# MP2456_EVM_V1.net
KiCad netlist of a schematic drawn in EAGLE
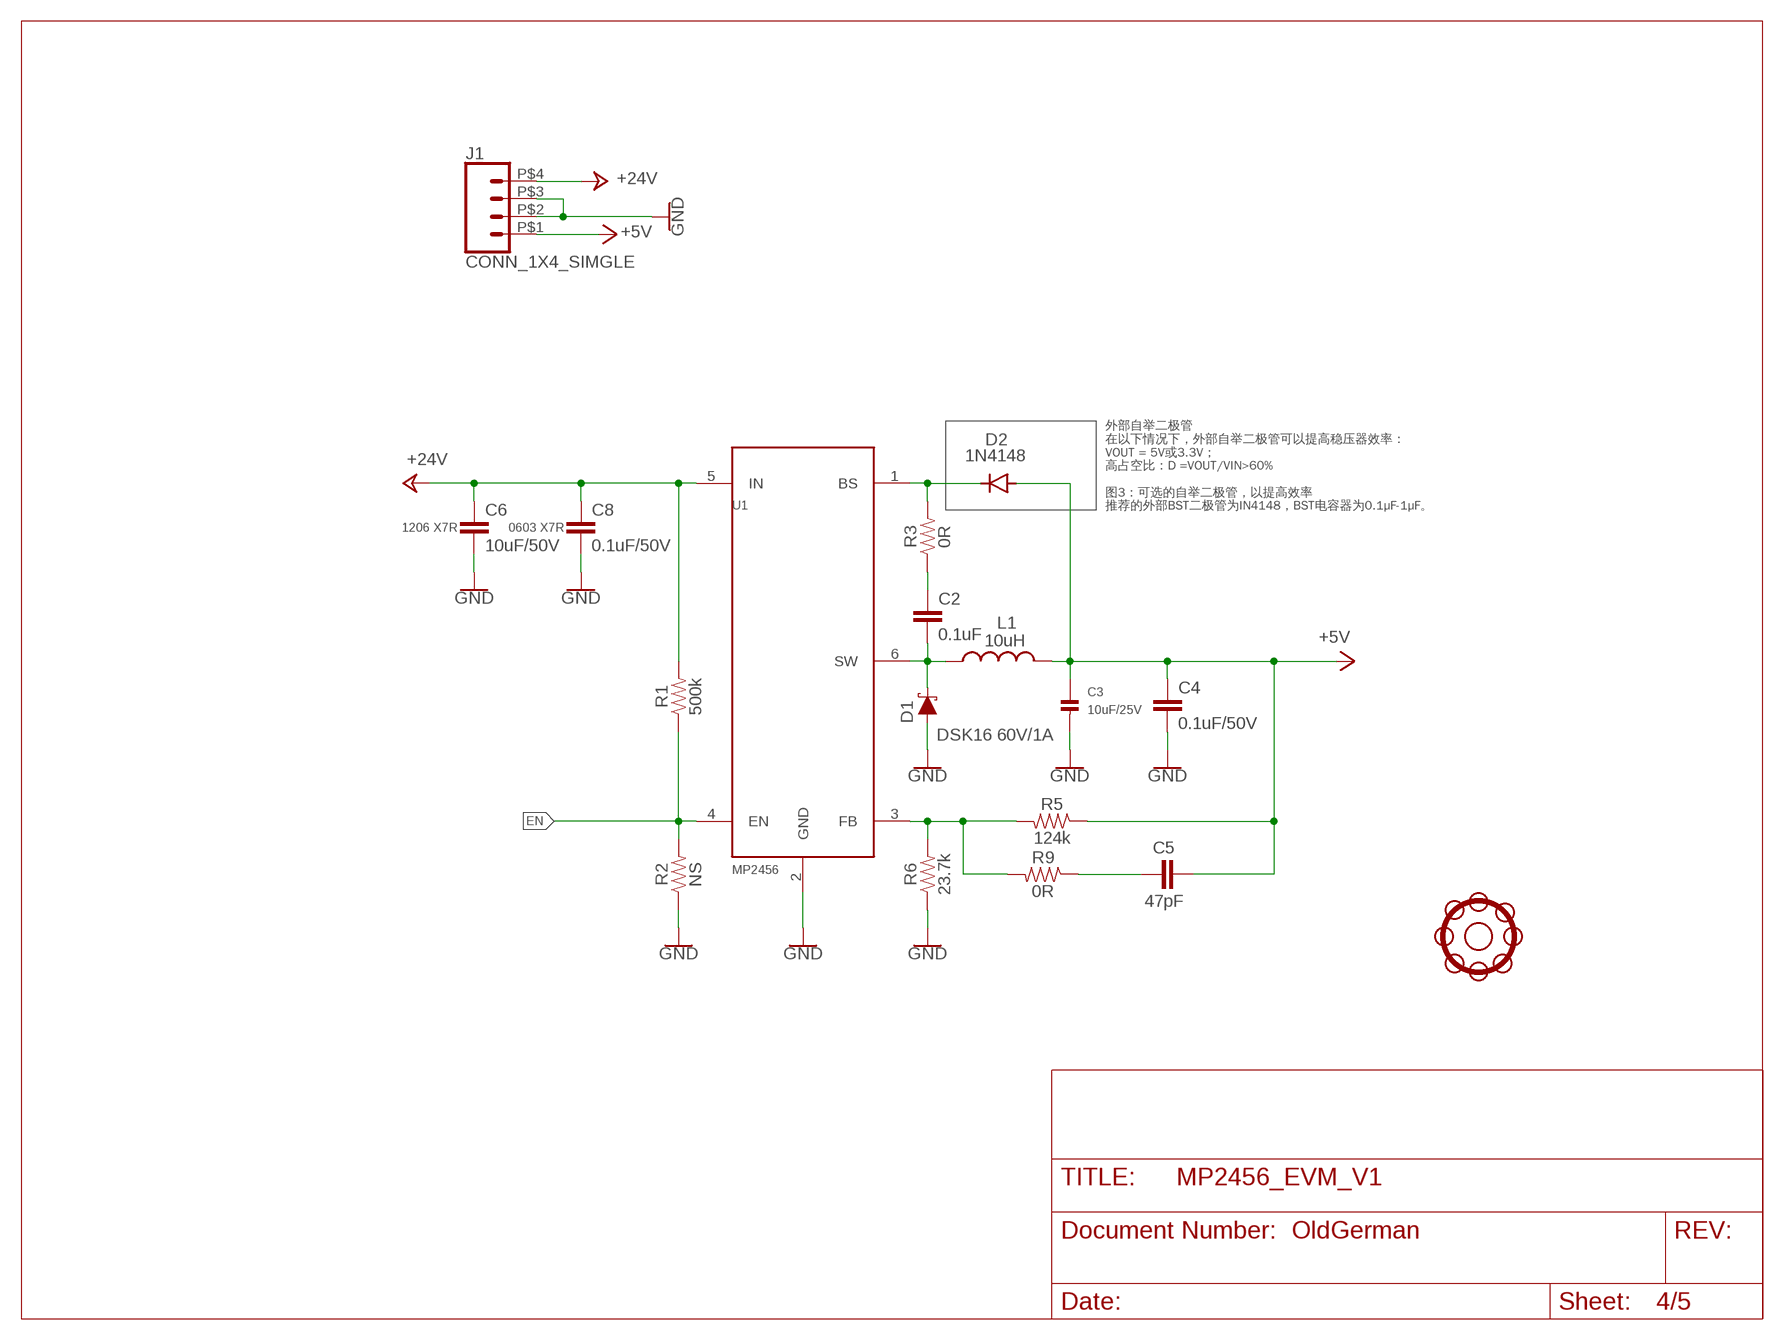
[diagram p0: schematic, sheet 4]

(export (version "E")
  (design (tool "Eeschema 10.0.6"))
  (components
    (comp (ref "C2")
      (value "0.1uF")
      (footprint "eagle-import:0603")
      (libsource (lib "eagle-import") (part "CAP-0603"))
    )
    (comp (ref "C3")
      (value "10uF/25V")
      (footprint "eagle-import:_0805MP")
      (libsource (lib "eagle-import") (part "CAP_CERAMIC_0805MP"))
    )
    (comp (ref "C4")
      (value "0.1uF/50V")
      (footprint "eagle-import:0603")
      (libsource (lib "eagle-import") (part "CAP-0603"))
    )
    (comp (ref "C5")
      (value "47pF")
      (footprint "eagle-import:0603")
      (libsource (lib "eagle-import") (part "CAP-0603"))
    )
    (comp (ref "C6")
      (value "10uF/50V")
      (footprint "eagle-import:1206")
      (libsource (lib "eagle-import") (part "CAP-1206"))
    )
    (comp (ref "C8")
      (value "0.1uF/50V")
      (footprint "eagle-import:0603")
      (libsource (lib "eagle-import") (part "CAP-0603"))
    )
    (comp (ref "D1")
      (value "DSK16 60V/1A")
      (footprint "eagle-import:SOD123")
      (libsource (lib "eagle-import") (part "B5819W-SOD123"))
    )
    (comp (ref "D2")
      (value "1N4148")
      (footprint "eagle-import:SOD123")
      (libsource (lib "eagle-import") (part "DIODE-SOD123"))
    )
    (comp (ref "J1")
      (value "CONN_1X4_SIMGLE")
      (footprint "eagle-import:CONN_1X04_SINGLE")
      (libsource (lib "eagle-import") (part "CONN_1X4_SIMGLE"))
    )
    (comp (ref "L1")
      (value "10uH")
      (footprint "eagle-import:4020TYPE")
      (libsource (lib "eagle-import") (part "INDUCTOR_4040"))
    )
    (comp (ref "R1")
      (value "500k")
      (footprint "eagle-import:0603")
      (libsource (lib "eagle-import") (part "RESISTOR0603"))
    )
    (comp (ref "R2")
      (value "NS")
      (footprint "eagle-import:0603")
      (libsource (lib "eagle-import") (part "RESISTOR0603"))
    )
    (comp (ref "R3")
      (value "0R")
      (footprint "eagle-import:0603")
      (libsource (lib "eagle-import") (part "RESISTOR0603"))
    )
    (comp (ref "R5")
      (value "124k")
      (footprint "eagle-import:0603")
      (libsource (lib "eagle-import") (part "RESISTOR0603"))
    )
    (comp (ref "R6")
      (value "23.7k")
      (footprint "eagle-import:0603")
      (libsource (lib "eagle-import") (part "RESISTOR0603"))
    )
    (comp (ref "R9")
      (value "0R")
      (footprint "eagle-import:0603")
      (libsource (lib "eagle-import") (part "RESISTOR0603"))
    )
    (comp (ref "U$1")
      (value "SUN_HOLE_M3")
      (footprint "eagle-import:SUN_HOLE_M3")
      (libsource (lib "eagle-import") (part "SUN_HOLE_M3"))
    )
    (comp (ref "U1")
      (value "MP2456")
      (footprint "eagle-import:SOT23-6")
      (libsource (lib "eagle-import") (part "MP2456"))
    )
  )
  (nets
    (net (code "1") (name "+5V") (class "Default")
      (node (ref "C3") (pin "1") (pinfunction "P$1_1") (pintype "passive"))
      (node (ref "C4") (pin "1") (pinfunction "1_1") (pintype "passive"))
      (node (ref "C5") (pin "2") (pinfunction "2_2") (pintype "passive"))
      (node (ref "D2") (pin "A") (pinfunction "A_A") (pintype "passive"))
      (node (ref "J1") (pin "P$1") (pinfunction "1_P$1") (pintype "passive"))
      (node (ref "L1") (pin "P$2") (pinfunction "2_P$2") (pintype "passive"))
      (node (ref "R5") (pin "1") (pinfunction "1_1") (pintype "passive"))
    )
    (net (code "2") (name "+24V") (class "Default")
      (node (ref "C6") (pin "1") (pinfunction "1_1") (pintype "passive"))
      (node (ref "C8") (pin "1") (pinfunction "1_1") (pintype "passive"))
      (node (ref "J1") (pin "P$4") (pinfunction "4_P$4") (pintype "passive"))
      (node (ref "R1") (pin "2") (pinfunction "2_2") (pintype "passive"))
      (node (ref "U1") (pin "5") (pinfunction "IN_5") (pintype "bidirectional"))
    )
    (net (code "3") (name "EN") (class "Default")
      (node (ref "R1") (pin "1") (pinfunction "1_1") (pintype "passive"))
      (node (ref "R2") (pin "2") (pinfunction "2_2") (pintype "passive"))
      (node (ref "U1") (pin "4") (pinfunction "EN_4") (pintype "bidirectional"))
    )
    (net (code "4") (name "GND") (class "Default")
      (node (ref "C3") (pin "2") (pinfunction "P$2_2") (pintype "passive"))
      (node (ref "C4") (pin "2") (pinfunction "2_2") (pintype "passive"))
      (node (ref "C6") (pin "2") (pinfunction "2_2") (pintype "passive"))
      (node (ref "C8") (pin "2") (pinfunction "2_2") (pintype "passive"))
      (node (ref "D1") (pin "A") (pinfunction "A_A") (pintype "passive"))
      (node (ref "J1") (pin "P$2") (pinfunction "2_P$2") (pintype "passive"))
      (node (ref "J1") (pin "P$3") (pinfunction "3_P$3") (pintype "passive"))
      (node (ref "R2") (pin "1") (pinfunction "1_1") (pintype "passive"))
      (node (ref "R6") (pin "1") (pinfunction "1_1") (pintype "passive"))
      (node (ref "U1") (pin "2") (pinfunction "GND_2") (pintype "bidirectional"))
    )
    (net (code "5") (name "Net-(C2-Pad1)") (class "Default")
      (node (ref "C2") (pin "1") (pinfunction "1_1") (pintype "passive"))
      (node (ref "R3") (pin "1") (pinfunction "1_1") (pintype "passive"))
    )
    (net (code "6") (name "Net-(C5-Pad1)") (class "Default")
      (node (ref "C5") (pin "1") (pinfunction "1_1") (pintype "passive"))
      (node (ref "R9") (pin "1") (pinfunction "1_1") (pintype "passive"))
    )
    (net (code "7") (name "Net-(L1-1)") (class "Default")
      (node (ref "C2") (pin "2") (pinfunction "2_2") (pintype "passive"))
      (node (ref "D1") (pin "C") (pinfunction "C_C") (pintype "passive"))
      (node (ref "L1") (pin "P$1") (pinfunction "1_P$1") (pintype "passive"))
      (node (ref "U1") (pin "6") (pinfunction "SW_6") (pintype "bidirectional"))
    )
    (net (code "8") (name "Net-(U1-BS)") (class "Default")
      (node (ref "D2") (pin "C") (pinfunction "C_C") (pintype "passive"))
      (node (ref "R3") (pin "2") (pinfunction "2_2") (pintype "passive"))
      (node (ref "U1") (pin "1") (pinfunction "BS_1") (pintype "bidirectional"))
    )
    (net (code "9") (name "Net-(U1-FB)") (class "Default")
      (node (ref "R5") (pin "2") (pinfunction "2_2") (pintype "passive"))
      (node (ref "R6") (pin "2") (pinfunction "2_2") (pintype "passive"))
      (node (ref "R9") (pin "2") (pinfunction "2_2") (pintype "passive"))
      (node (ref "U1") (pin "3") (pinfunction "FB_3") (pintype "bidirectional"))
    )
  )
)
